# RoboSkinRev1.net
KiCad netlist of a schematic drawn in EAGLE
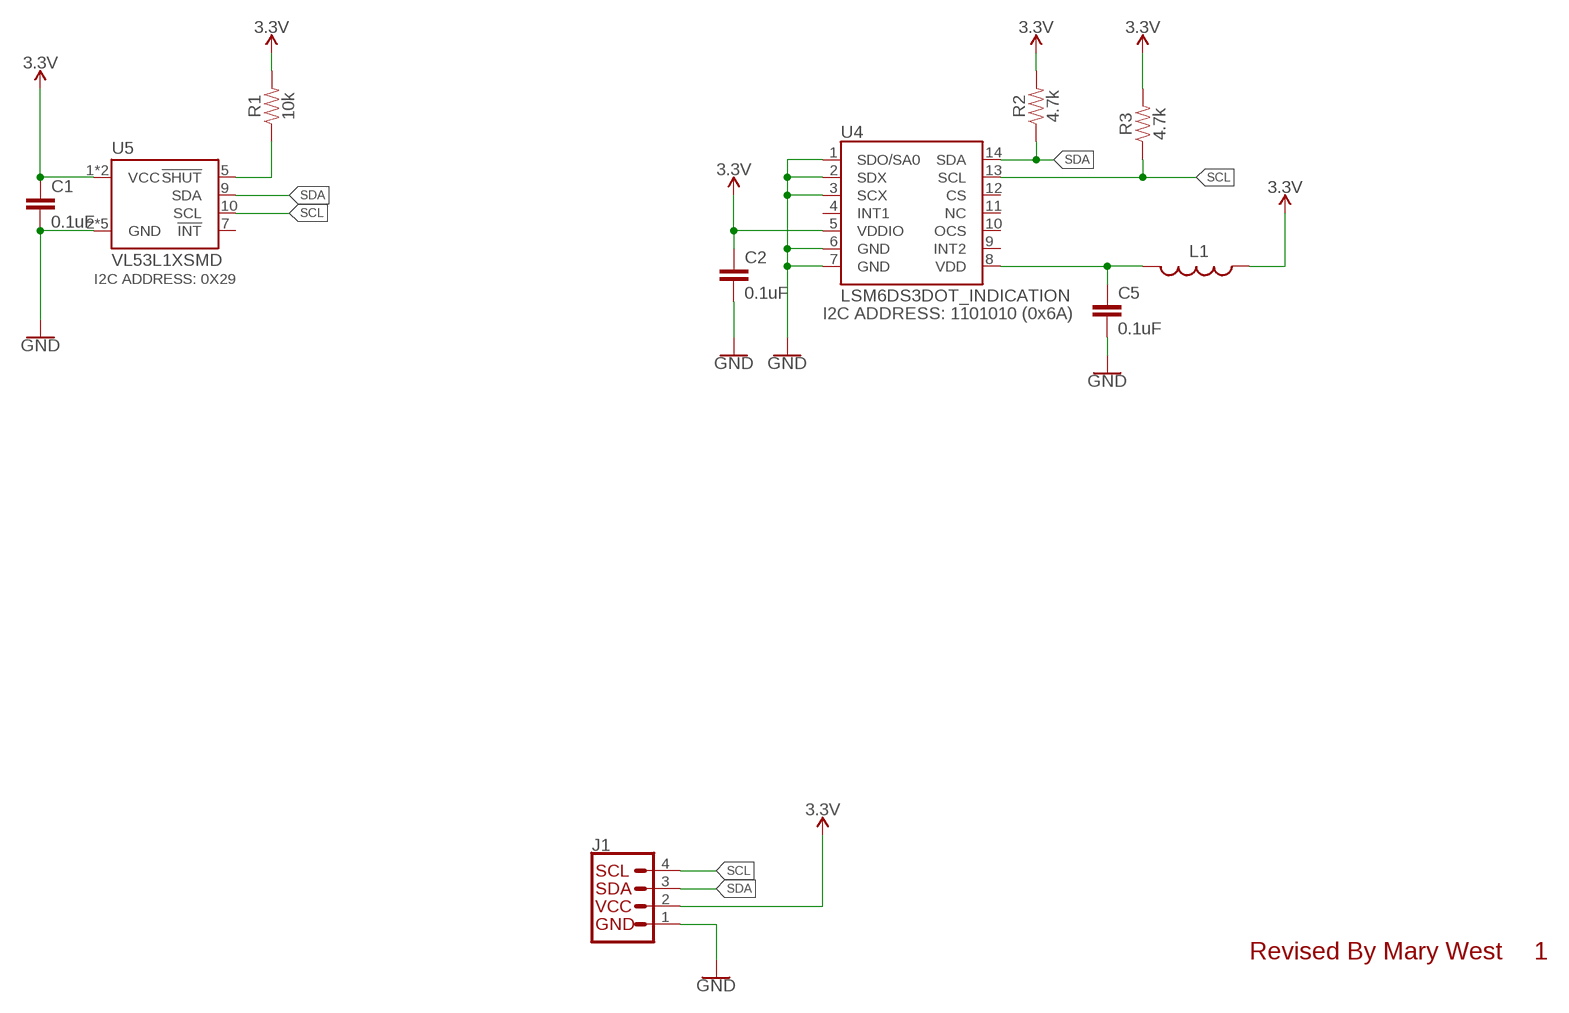
[diagram p0: schematic, sheet 1]

(export (version "E")
  (design (tool "Eeschema 10.0.6"))
  (components
    (comp (ref "C1")
      (value "0.1uF")
      (footprint "eagle-import:0603")
      (libsource (lib "eagle-import") (part "0.1UF-0603-25V-(+80/-20%)"))
    )
    (comp (ref "C2")
      (value "0.1uF")
      (footprint "eagle-import:0603")
      (libsource (lib "eagle-import") (part "0.1UF-0603-25V-(+80/-20%)"))
    )
    (comp (ref "C5")
      (value "0.1uF")
      (footprint "eagle-import:0603")
      (libsource (lib "eagle-import") (part "0.1UF-0603-25V-(+80/-20%)"))
    )
    (comp (ref "J1")
      (value "QWIIC_CONNECTORJS-1MM")
      (footprint "eagle-import:1X04_1MM_RA")
      (libsource (lib "eagle-import") (part "QWIIC_CONNECTORJS-1MM"))
    )
    (comp (ref "L1")
      (value "RES-07859")
      (footprint "eagle-import:0603")
      (libsource (lib "eagle-import") (part "INDUCTOR30OHM,1.8A"))
    )
    (comp (ref "R1")
      (value "10k")
      (footprint "eagle-import:0603")
      (libsource (lib "eagle-import") (part "10KOHM-0603-1/10W-1%"))
    )
    (comp (ref "R2")
      (value "4.7k")
      (footprint "eagle-import:0603")
      (libsource (lib "eagle-import") (part "4.7KOHM-0603-1/10W-1%"))
    )
    (comp (ref "R3")
      (value "4.7k")
      (footprint "eagle-import:0603")
      (libsource (lib "eagle-import") (part "4.7KOHM-0603-1/10W-1%"))
    )
    (comp (ref "U4")
      (value "LSM6DS3DOT_INDICATION")
      (footprint "eagle-import:LGA14L_DOT_INDICATOR")
      (libsource (lib "eagle-import") (part "LSM6DS3DOT_INDICATION"))
    )
    (comp (ref "U5")
      (value "VL53L1XSMD")
      (footprint "eagle-import:VL53L1X")
      (libsource (lib "eagle-import") (part "VL53L1XSMD"))
    )
  )
  (nets
    (net (code "1") (name "3.3V") (class "Default")
      (node (ref "C1") (pin "1") (pinfunction "1_1") (pintype "passive"))
      (node (ref "C2") (pin "1") (pinfunction "1_1") (pintype "passive"))
      (node (ref "J1") (pin "2") (pinfunction "VCC_2") (pintype "power_in"))
      (node (ref "L1") (pin "1") (pinfunction "1_1") (pintype "passive"))
      (node (ref "R1") (pin "2") (pinfunction "2_2") (pintype "passive"))
      (node (ref "R2") (pin "2") (pinfunction "2_2") (pintype "passive"))
      (node (ref "R3") (pin "2") (pinfunction "2_2") (pintype "passive"))
      (node (ref "U4") (pin "5") (pinfunction "VDDIO_5") (pintype "bidirectional"))
      (node (ref "U5") (pin "1") (pinfunction "VCC_1") (pintype "bidirectional"))
      (node (ref "U5") (pin "11") (pinfunction "VCC_11") (pintype "bidirectional"))
    )
    (net (code "2") (name "GND") (class "Default")
      (node (ref "C1") (pin "2") (pinfunction "2_2") (pintype "passive"))
      (node (ref "C2") (pin "2") (pinfunction "2_2") (pintype "passive"))
      (node (ref "C5") (pin "2") (pinfunction "2_2") (pintype "passive"))
      (node (ref "J1") (pin "1") (pinfunction "GND_1") (pintype "power_in"))
      (node (ref "U4") (pin "1") (pinfunction "SDO/SA0_1") (pintype "bidirectional"))
      (node (ref "U4") (pin "2") (pinfunction "SDX_2") (pintype "bidirectional"))
      (node (ref "U4") (pin "3") (pinfunction "SCX_3") (pintype "bidirectional"))
      (node (ref "U4") (pin "6") (pinfunction "GND_6") (pintype "bidirectional"))
      (node (ref "U4") (pin "7") (pinfunction "GND_7") (pintype "bidirectional"))
      (node (ref "U5") (pin "12") (pinfunction "GND_12") (pintype "bidirectional"))
      (node (ref "U5") (pin "2") (pinfunction "GND_2") (pintype "bidirectional"))
      (node (ref "U5") (pin "3") (pinfunction "GND_3") (pintype "bidirectional"))
      (node (ref "U5") (pin "4") (pinfunction "GND_4") (pintype "bidirectional"))
      (node (ref "U5") (pin "6") (pinfunction "GND_6") (pintype "bidirectional"))
    )
    (net (code "3") (name "Net-(U4-VDD)") (class "Default")
      (node (ref "C5") (pin "1") (pinfunction "1_1") (pintype "passive"))
      (node (ref "L1") (pin "2") (pinfunction "2_2") (pintype "passive"))
      (node (ref "U4") (pin "8") (pinfunction "VDD_8") (pintype "bidirectional"))
    )
    (net (code "4") (name "Net-(U5-~{SHUT})") (class "Default")
      (node (ref "R1") (pin "1") (pinfunction "1_1") (pintype "passive"))
      (node (ref "U5") (pin "5") (pinfunction "~{SHUT}_5") (pintype "bidirectional"))
    )
    (net (code "5") (name "SCL") (class "Default")
      (node (ref "J1") (pin "4") (pinfunction "SCL_4") (pintype "passive"))
      (node (ref "R3") (pin "1") (pinfunction "1_1") (pintype "passive"))
      (node (ref "U4") (pin "13") (pinfunction "SCL_13") (pintype "bidirectional"))
      (node (ref "U5") (pin "10") (pinfunction "SCL_10") (pintype "bidirectional"))
    )
    (net (code "6") (name "SDA") (class "Default")
      (node (ref "J1") (pin "3") (pinfunction "SDA_3") (pintype "passive"))
      (node (ref "R2") (pin "1") (pinfunction "1_1") (pintype "passive"))
      (node (ref "U4") (pin "14") (pinfunction "SDA_14") (pintype "bidirectional"))
      (node (ref "U5") (pin "9") (pinfunction "SDA_9") (pintype "bidirectional"))
    )
    (net (code "7") (name "unconnected-(U4-CS-Pad12)") (class "Default")
      (node (ref "U4") (pin "12") (pinfunction "CS_12") (pintype "bidirectional"))
    )
    (net (code "8") (name "unconnected-(U4-INT1-Pad4)") (class "Default")
      (node (ref "U4") (pin "4") (pinfunction "INT1_4") (pintype "bidirectional"))
    )
    (net (code "9") (name "unconnected-(U4-INT2-Pad9)") (class "Default")
      (node (ref "U4") (pin "9") (pinfunction "INT2_9") (pintype "bidirectional"))
    )
    (net (code "10") (name "unconnected-(U4-NC-Pad11)") (class "Default")
      (node (ref "U4") (pin "11") (pinfunction "NC_11") (pintype "bidirectional"))
    )
    (net (code "11") (name "unconnected-(U4-OCS-Pad10)") (class "Default")
      (node (ref "U4") (pin "10") (pinfunction "OCS_10") (pintype "bidirectional"))
    )
    (net (code "12") (name "unconnected-(U5-~{INT}-Pad7)") (class "Default")
      (node (ref "U5") (pin "7") (pinfunction "~{INT}_7") (pintype "bidirectional"))
    )
  )
)
